# sensor.net
KiCad netlist of a schematic drawn in Altium Designer
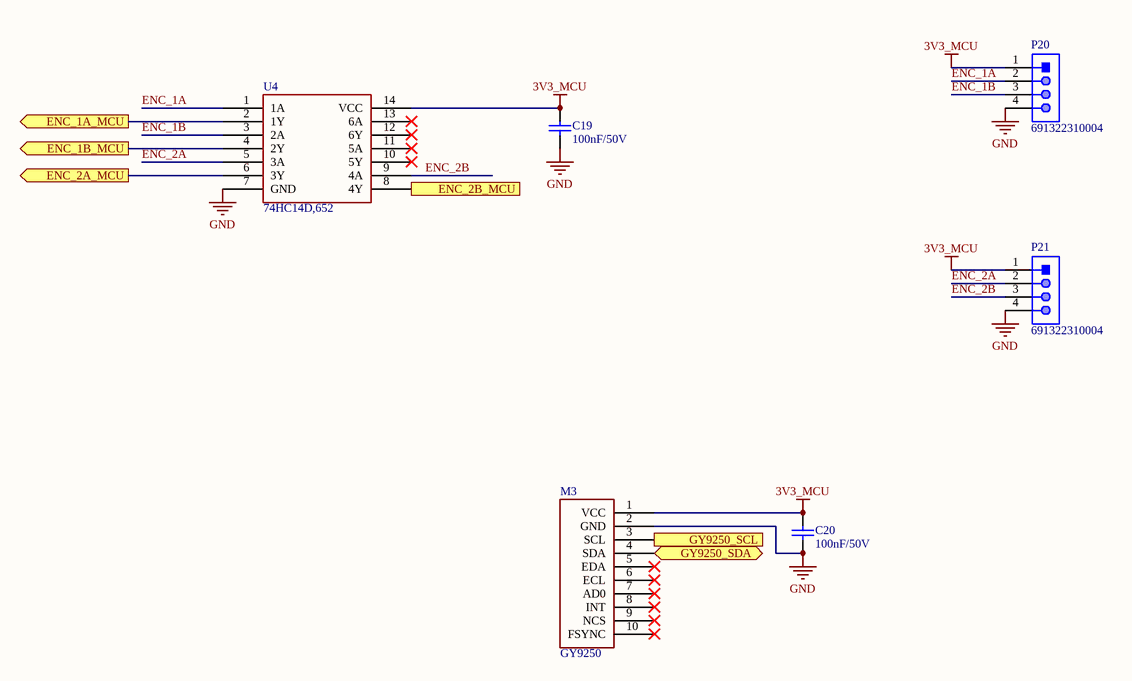
[diagram p0: sensor.SchDoc]

(export (version "E")
  (design (tool "Eeschema 10.0.6"))
  (components
    (comp (ref "C19")
      (value "100nF/50V")
      (footprint "CAP-SM-0805")
      (description "CAP CER 0.1UF 50V Y5V 0805")
      (fields
        (field (name "MANUFACTURER") "Samsung Electro-Mechanics")
        (field (name "MANUFACTURER PART NUMBER") "CL21F104ZBCNNNC")
      )
      (libsource (lib "Capacitor") (part "Cap-100nF-50V-0805"))
    )
    (comp (ref "C20")
      (value "100nF/50V")
      (footprint "CAP-SM-0805")
      (description "CAP CER 0.1UF 50V Y5V 0805")
      (fields
        (field (name "MANUFACTURER") "Samsung Electro-Mechanics")
        (field (name "MANUFACTURER PART NUMBER") "CL21F104ZBCNNNC")
      )
      (libsource (lib "Capacitor") (part "Cap-100nF-50V-0805"))
    )
    (comp (ref "M3") (value "GY9250") (footprint "GY9250") (libsource (lib "PIFWRobot") (part "GY9250")))
    (comp (ref "P20")
      (value "691322310004")
      (footprint "691322310004")
      (description "WR-TBL Serie 322 Horizontal PCB Header, Pluggable, pitch 3.81mm, 4p")
      (fields (field (name "LOCAL SUPLIER PART NUMBER") "x") (field (name "PUBLISHER") "Wurth Elektronik"))
      (libsource (lib "terminal_block") (part "691322310004"))
    )
    (comp (ref "P21")
      (value "691322310004")
      (footprint "691322310004")
      (description "WR-TBL Serie 322 Horizontal PCB Header, Pluggable, pitch 3.81mm, 4p")
      (fields (field (name "LOCAL SUPLIER PART NUMBER") "x") (field (name "PUBLISHER") "Wurth Elektronik"))
      (libsource (lib "terminal_block") (part "691322310004"))
    )
    (comp (ref "U4")
      (value "74HC14D,652")
      (footprint "SOT108-1_NEX")
      (fields (field (name "COPYRIGHT") "Copyright (C) 2016 Accelerated Designs. All rights reserved"))
      (libsource (lib "PIFWRobot") (part "74HC14D,652"))
    )
  )
  (nets
    (net (code "1") (name "/ENC_1A") (class "Default")
      (node (ref "P20") (pin "2") (pinfunction "2_2") (pintype "passive"))
      (node (ref "U4") (pin "1") (pinfunction "1A_1") (pintype "passive"))
    )
    (net (code "2") (name "/ENC_1A_MCU") (class "Default")
      (node (ref "U4") (pin "2") (pinfunction "1Y_2") (pintype "passive"))
    )
    (net (code "3") (name "/ENC_1B") (class "Default")
      (node (ref "P20") (pin "3") (pinfunction "3_3") (pintype "passive"))
      (node (ref "U4") (pin "3") (pinfunction "2A_3") (pintype "passive"))
    )
    (net (code "4") (name "/ENC_1B_MCU") (class "Default")
      (node (ref "U4") (pin "4") (pinfunction "2Y_4") (pintype "passive"))
    )
    (net (code "5") (name "/ENC_2A") (class "Default")
      (node (ref "P21") (pin "2") (pinfunction "2_2") (pintype "passive"))
      (node (ref "U4") (pin "5") (pinfunction "3A_5") (pintype "passive"))
    )
    (net (code "6") (name "/ENC_2A_MCU") (class "Default")
      (node (ref "U4") (pin "6") (pinfunction "3Y_6") (pintype "passive"))
    )
    (net (code "7") (name "/ENC_2B") (class "Default")
      (node (ref "P21") (pin "3") (pinfunction "3_3") (pintype "passive"))
      (node (ref "U4") (pin "9") (pinfunction "4A_9") (pintype "passive"))
    )
    (net (code "8") (name "/ENC_2B_MCU") (class "Default")
      (node (ref "U4") (pin "8") (pinfunction "4Y_8") (pintype "passive"))
    )
    (net (code "9") (name "/GY9250_SCL") (class "Default")
      (node (ref "M3") (pin "3") (pinfunction "SCL_3") (pintype "passive"))
    )
    (net (code "10") (name "/GY9250_SDA") (class "Default")
      (node (ref "M3") (pin "4") (pinfunction "SDA_4") (pintype "passive"))
    )
    (net (code "11") (name "3V3_MCU") (class "Default")
      (node (ref "C19") (pin "2") (pinfunction "2_2") (pintype "passive"))
      (node (ref "C20") (pin "2") (pinfunction "2_2") (pintype "passive"))
      (node (ref "M3") (pin "1") (pinfunction "VCC_1") (pintype "passive"))
      (node (ref "P20") (pin "1") (pinfunction "1_1") (pintype "passive"))
      (node (ref "P21") (pin "1") (pinfunction "1_1") (pintype "passive"))
      (node (ref "U4") (pin "14") (pinfunction "VCC_14") (pintype "passive"))
    )
    (net (code "12") (name "GND") (class "Default")
      (node (ref "C19") (pin "1") (pinfunction "1_1") (pintype "passive"))
      (node (ref "C20") (pin "1") (pinfunction "1_1") (pintype "passive"))
      (node (ref "M3") (pin "2") (pinfunction "GND_2") (pintype "passive"))
      (node (ref "P20") (pin "4") (pinfunction "4_4") (pintype "passive"))
      (node (ref "P21") (pin "4") (pinfunction "4_4") (pintype "passive"))
      (node (ref "U4") (pin "7") (pinfunction "GND_7") (pintype "passive"))
    )
    (net (code "13") (name "unconnected-(M3-AD0-Pad7)") (class "Default")
      (node (ref "M3") (pin "7") (pinfunction "AD0_7") (pintype "passive+no_connect"))
    )
    (net (code "14") (name "unconnected-(M3-ECL-Pad6)") (class "Default")
      (node (ref "M3") (pin "6") (pinfunction "ECL_6") (pintype "passive+no_connect"))
    )
    (net (code "15") (name "unconnected-(M3-EDA-Pad5)") (class "Default")
      (node (ref "M3") (pin "5") (pinfunction "EDA_5") (pintype "passive+no_connect"))
    )
    (net (code "16") (name "unconnected-(M3-FSYNC-Pad10)") (class "Default")
      (node (ref "M3") (pin "10") (pinfunction "FSYNC_10") (pintype "passive+no_connect"))
    )
    (net (code "17") (name "unconnected-(M3-INT-Pad8)") (class "Default")
      (node (ref "M3") (pin "8") (pinfunction "INT_8") (pintype "passive+no_connect"))
    )
    (net (code "18") (name "unconnected-(M3-NCS-Pad9)") (class "Default")
      (node (ref "M3") (pin "9") (pinfunction "NCS_9") (pintype "passive+no_connect"))
    )
    (net (code "19") (name "unconnected-(U4-5A-Pad11)") (class "Default")
      (node (ref "U4") (pin "11") (pinfunction "5A_11") (pintype "passive+no_connect"))
    )
    (net (code "20") (name "unconnected-(U4-5Y-Pad10)") (class "Default")
      (node (ref "U4") (pin "10") (pinfunction "5Y_10") (pintype "passive+no_connect"))
    )
    (net (code "21") (name "unconnected-(U4-6A-Pad13)") (class "Default")
      (node (ref "U4") (pin "13") (pinfunction "6A_13") (pintype "passive+no_connect"))
    )
    (net (code "22") (name "unconnected-(U4-6Y-Pad12)") (class "Default")
      (node (ref "U4") (pin "12") (pinfunction "6Y_12") (pintype "passive+no_connect"))
    )
  )
)
